# STX3NoAnt.net
KiCad netlist of a schematic drawn in EAGLE
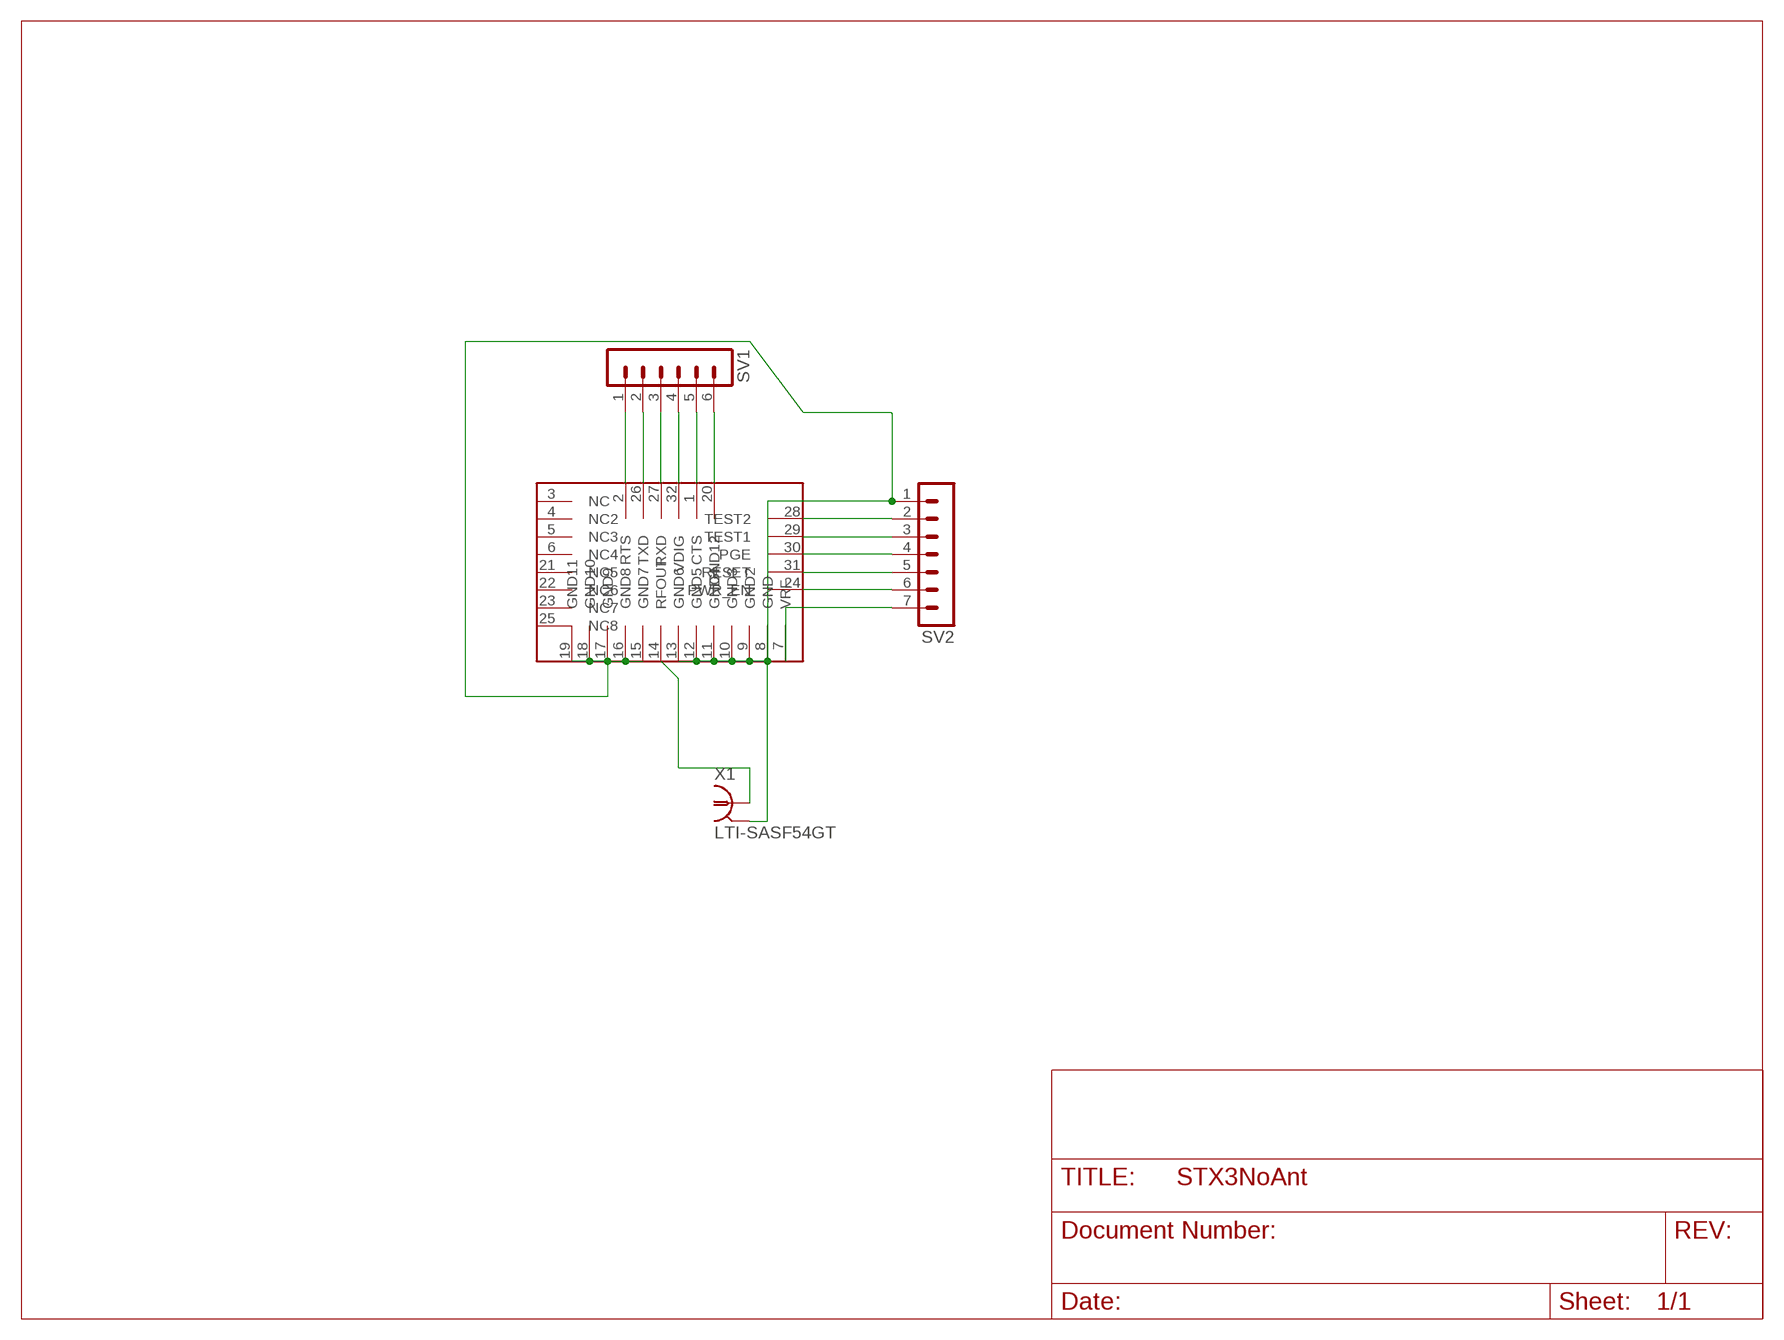
[diagram p0: schematic, sheet 1]

(export (version "E")
  (design (tool "Eeschema 10.0.6"))
  (components
    (comp (ref "SV1")
      (value "MA06-1")
      (footprint "eagle-import:MA06-1")
      (libsource (lib "eagle-import") (part "MA06-1"))
    )
    (comp (ref "SV2")
      (value "MA07-1")
      (footprint "eagle-import:MA07-1")
      (libsource (lib "eagle-import") (part "MA07-1"))
    )
    (comp (ref "U$1")
      (value "STX3")
      (footprint "eagle-import:STX3")
      (libsource (lib "eagle-import") (part "STX3"))
    )
    (comp (ref "X1")
      (value "LTI-SASF54GT")
      (footprint "eagle-import:LTI-SASF54GT")
      (libsource (lib "eagle-import") (part "LTI-SASF54GT"))
    )
  )
  (nets
    (net (code "1") (name "Net-(U$1-CTS)") (class "Default")
      (node (ref "SV1") (pin "5") (pinfunction "5_5") (pintype "passive"))
      (node (ref "U$1") (pin "1") (pinfunction "CTS_1") (pintype "bidirectional"))
    )
    (net (code "2") (name "Net-(U$1-GND)") (class "Default")
      (node (ref "SV2") (pin "1") (pinfunction "1_1") (pintype "passive"))
      (node (ref "U$1") (pin "10") (pinfunction "GND3_10") (pintype "bidirectional"))
      (node (ref "U$1") (pin "11") (pinfunction "GND4_11") (pintype "bidirectional"))
      (node (ref "U$1") (pin "12") (pinfunction "GND5_12") (pintype "bidirectional"))
      (node (ref "U$1") (pin "13") (pinfunction "GND6_13") (pintype "bidirectional"))
      (node (ref "U$1") (pin "15") (pinfunction "GND7_15") (pintype "bidirectional"))
      (node (ref "U$1") (pin "16") (pinfunction "GND8_16") (pintype "bidirectional"))
      (node (ref "U$1") (pin "17") (pinfunction "GND9_17") (pintype "bidirectional"))
      (node (ref "U$1") (pin "18") (pinfunction "GND10_18") (pintype "bidirectional"))
      (node (ref "U$1") (pin "19") (pinfunction "GND11_19") (pintype "bidirectional"))
      (node (ref "U$1") (pin "8") (pinfunction "GND_8") (pintype "bidirectional"))
      (node (ref "U$1") (pin "9") (pinfunction "GND2_9") (pintype "bidirectional"))
      (node (ref "X1") (pin "2") (pinfunction "2_2") (pintype "passive"))
      (node (ref "X1") (pin "3") (pinfunction "2_3") (pintype "passive"))
      (node (ref "X1") (pin "4") (pinfunction "2_4") (pintype "passive"))
      (node (ref "X1") (pin "5") (pinfunction "2_5") (pintype "passive"))
    )
    (net (code "3") (name "Net-(U$1-GND12)") (class "Default")
      (node (ref "SV1") (pin "6") (pinfunction "6_6") (pintype "passive"))
      (node (ref "U$1") (pin "20") (pinfunction "GND12_20") (pintype "bidirectional"))
    )
    (net (code "4") (name "Net-(U$1-PGE)") (class "Default")
      (node (ref "SV2") (pin "4") (pinfunction "4_4") (pintype "passive"))
      (node (ref "U$1") (pin "30") (pinfunction "PGE_30") (pintype "bidirectional"))
    )
    (net (code "5") (name "Net-(U$1-PWR_EN)") (class "Default")
      (node (ref "SV2") (pin "6") (pinfunction "6_6") (pintype "passive"))
      (node (ref "U$1") (pin "24") (pinfunction "PWR_EN_24") (pintype "bidirectional"))
    )
    (net (code "6") (name "Net-(U$1-RESET)") (class "Default")
      (node (ref "SV2") (pin "5") (pinfunction "5_5") (pintype "passive"))
      (node (ref "U$1") (pin "31") (pinfunction "RESET_31") (pintype "bidirectional"))
    )
    (net (code "7") (name "Net-(U$1-RFOUT)") (class "Default")
      (node (ref "U$1") (pin "14") (pinfunction "RFOUT_14") (pintype "bidirectional"))
      (node (ref "X1") (pin "1") (pinfunction "1_1") (pintype "passive"))
    )
    (net (code "8") (name "Net-(U$1-RTS)") (class "Default")
      (node (ref "SV1") (pin "1") (pinfunction "1_1") (pintype "passive"))
      (node (ref "U$1") (pin "2") (pinfunction "RTS_2") (pintype "bidirectional"))
    )
    (net (code "9") (name "Net-(U$1-RXD)") (class "Default")
      (node (ref "SV1") (pin "3") (pinfunction "3_3") (pintype "passive"))
      (node (ref "U$1") (pin "27") (pinfunction "RXD_27") (pintype "bidirectional"))
    )
    (net (code "10") (name "Net-(U$1-TEST1)") (class "Default")
      (node (ref "SV2") (pin "3") (pinfunction "3_3") (pintype "passive"))
      (node (ref "U$1") (pin "29") (pinfunction "TEST1_29") (pintype "bidirectional"))
    )
    (net (code "11") (name "Net-(U$1-TEST2)") (class "Default")
      (node (ref "SV2") (pin "2") (pinfunction "2_2") (pintype "passive"))
      (node (ref "U$1") (pin "28") (pinfunction "TEST2_28") (pintype "bidirectional"))
    )
    (net (code "12") (name "Net-(U$1-TXD)") (class "Default")
      (node (ref "SV1") (pin "2") (pinfunction "2_2") (pintype "passive"))
      (node (ref "U$1") (pin "26") (pinfunction "TXD_26") (pintype "bidirectional"))
    )
    (net (code "13") (name "Net-(U$1-VDIG)") (class "Default")
      (node (ref "SV1") (pin "4") (pinfunction "4_4") (pintype "passive"))
      (node (ref "U$1") (pin "32") (pinfunction "VDIG_32") (pintype "bidirectional"))
    )
    (net (code "14") (name "Net-(U$1-VRF)") (class "Default")
      (node (ref "SV2") (pin "7") (pinfunction "7_7") (pintype "passive"))
      (node (ref "U$1") (pin "7") (pinfunction "VRF_7") (pintype "bidirectional"))
    )
    (net (code "15") (name "unconnected-(U$1-NC-Pad3)") (class "Default")
      (node (ref "U$1") (pin "3") (pinfunction "NC_3") (pintype "bidirectional"))
    )
    (net (code "16") (name "unconnected-(U$1-NC2-Pad4)") (class "Default")
      (node (ref "U$1") (pin "4") (pinfunction "NC2_4") (pintype "bidirectional"))
    )
    (net (code "17") (name "unconnected-(U$1-NC3-Pad5)") (class "Default")
      (node (ref "U$1") (pin "5") (pinfunction "NC3_5") (pintype "bidirectional"))
    )
    (net (code "18") (name "unconnected-(U$1-NC4-Pad6)") (class "Default")
      (node (ref "U$1") (pin "6") (pinfunction "NC4_6") (pintype "bidirectional"))
    )
    (net (code "19") (name "unconnected-(U$1-NC5-Pad21)") (class "Default")
      (node (ref "U$1") (pin "21") (pinfunction "NC5_21") (pintype "bidirectional"))
    )
    (net (code "20") (name "unconnected-(U$1-NC6-Pad22)") (class "Default")
      (node (ref "U$1") (pin "22") (pinfunction "NC6_22") (pintype "bidirectional"))
    )
    (net (code "21") (name "unconnected-(U$1-NC7-Pad23)") (class "Default")
      (node (ref "U$1") (pin "23") (pinfunction "NC7_23") (pintype "bidirectional"))
    )
    (net (code "22") (name "unconnected-(U$1-NC8-Pad25)") (class "Default")
      (node (ref "U$1") (pin "25") (pinfunction "NC8_25") (pintype "bidirectional"))
    )
  )
)
